# G22V3-LEDs.net
KiCad netlist of a schematic drawn in EAGLE
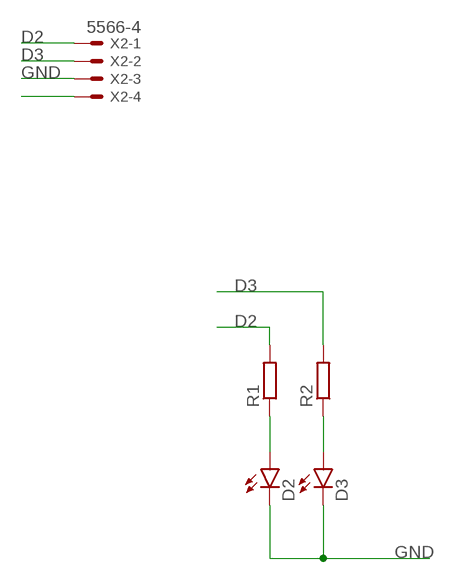
[diagram p0: schematic, sheet 1]

(export (version "E")
  (design (tool "Eeschema 10.0.6"))
  (components
    (comp (ref "D2")
      (value "LED5MM")
      (footprint "eagle-import:LED5MM")
      (libsource (lib "eagle-import") (part "LED5MM"))
    )
    (comp (ref "D3")
      (value "LED5MM")
      (footprint "eagle-import:LED5MM")
      (libsource (lib "eagle-import") (part "LED5MM"))
    )
    (comp (ref "R1")
      (value "R-EU_0204/7")
      (footprint "eagle-import:0204_7")
      (libsource (lib "eagle-import") (part "R-EU_0204/7"))
    )
    (comp (ref "R2")
      (value "R-EU_0204/7")
      (footprint "eagle-import:0204_7")
      (libsource (lib "eagle-import") (part "R-EU_0204/7"))
    )
    (comp (ref "X2")
      (value "5566-4")
      (footprint "eagle-import:5566-4")
      (fields (field (name "MF") "MOLEX"))
      (libsource (lib "eagle-import") (part "5566-4"))
    )
  )
  (nets
    (net (code "1") (name "/D2") (class "Default")
      (node (ref "R1") (pin "2") (pinfunction "2_2") (pintype "passive"))
      (node (ref "X2") (pin "1") (pinfunction "S_1") (pintype "passive"))
    )
    (net (code "2") (name "/D3") (class "Default")
      (node (ref "R2") (pin "2") (pinfunction "2_2") (pintype "passive"))
      (node (ref "X2") (pin "2") (pinfunction "S_2") (pintype "passive"))
    )
    (net (code "3") (name "/GND") (class "Default")
      (node (ref "D2") (pin "K") (pinfunction "C_K") (pintype "passive"))
      (node (ref "D3") (pin "K") (pinfunction "C_K") (pintype "passive"))
      (node (ref "X2") (pin "3") (pinfunction "S_3") (pintype "passive"))
    )
    (net (code "4") (name "Net-(D2-PadA)") (class "Default")
      (node (ref "D2") (pin "A") (pinfunction "A_A") (pintype "passive"))
      (node (ref "R1") (pin "1") (pinfunction "1_1") (pintype "passive"))
    )
    (net (code "5") (name "Net-(D3-PadA)") (class "Default")
      (node (ref "D3") (pin "A") (pinfunction "A_A") (pintype "passive"))
      (node (ref "R2") (pin "1") (pinfunction "1_1") (pintype "passive"))
    )
    (net (code "6") (name "unconnected-(X2D-S-Pad4)") (class "Default")
      (node (ref "X2") (pin "4") (pinfunction "S_4") (pintype "passive"))
    )
  )
)
